# IR_emit_recv.net
KiCad netlist of a schematic drawn in Altium Designer
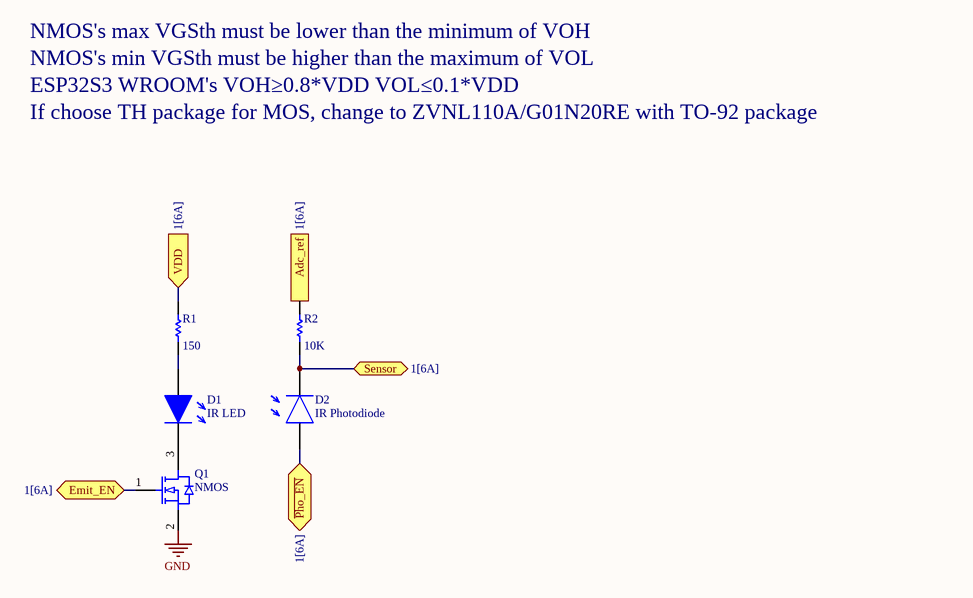
[diagram p0: IR emit recv.SchDoc]

(export (version "E")
  (design (tool "Eeschema 10.0.6"))
  (components
    (comp (ref "D1")
      (value "IR LED")
      (footprint "LED 3mm LH THT Clear")
      (description "发光二极管")
      (libsource (lib "My_Library") (part "LED"))
    )
    (comp (ref "D2")
      (value "IR Photodiode")
      (footprint "LED 3mm RH THT IRBlack")
      (libsource (lib "My_Library") (part "IR Photodiode"))
    )
    (comp (ref "Q1") (value "NMOS") (footprint "SOT23-3") (libsource (lib "My_Library") (part "NMOS")))
    (comp (ref "R1")
      (value "150")
      (footprint "0805 R/L")
      (fields (field (name "Comment") "Res"))
      (libsource (lib "My_Library") (part "Res"))
    )
    (comp (ref "R2")
      (value "10K")
      (footprint "0805 R/L")
      (fields (field (name "Comment") "Res"))
      (libsource (lib "My_Library") (part "Res"))
    )
  )
  (nets
    (net (code "1") (name "/Adc_ref") (class "Default") (node (ref "R2") (pin "2") (pintype "passive")))
    (net (code "2") (name "/Emit_EN") (class "Default")
      (node (ref "Q1") (pin "1") (pinfunction "G_1") (pintype "passive"))
    )
    (net (code "3") (name "/Sensor") (class "Default")
      (node (ref "D2") (pin "1") (pintype "passive"))
      (node (ref "R2") (pin "1") (pintype "passive"))
    )
    (net (code "4") (name "/VDD") (class "Default") (node (ref "R1") (pin "2") (pintype "passive")))
    (net (code "5") (name "/~{Pho_EN}") (class "Default") (node (ref "D2") (pin "2") (pintype "passive")))
    (net (code "6") (name "GND") (class "Default")
      (node (ref "Q1") (pin "2") (pinfunction "S_2") (pintype "passive"))
    )
    (net (code "7") (name "Net-(D1-Pad2)") (class "Default")
      (node (ref "D1") (pin "2") (pintype "passive"))
      (node (ref "R1") (pin "1") (pintype "passive"))
    )
    (net (code "8") (name "Net-(Q1-D)") (class "Default")
      (node (ref "D1") (pin "1") (pintype "passive"))
      (node (ref "Q1") (pin "3") (pinfunction "D_3") (pintype "passive"))
    )
  )
)
